# PDM.net
KiCad netlist of a schematic drawn in EAGLE
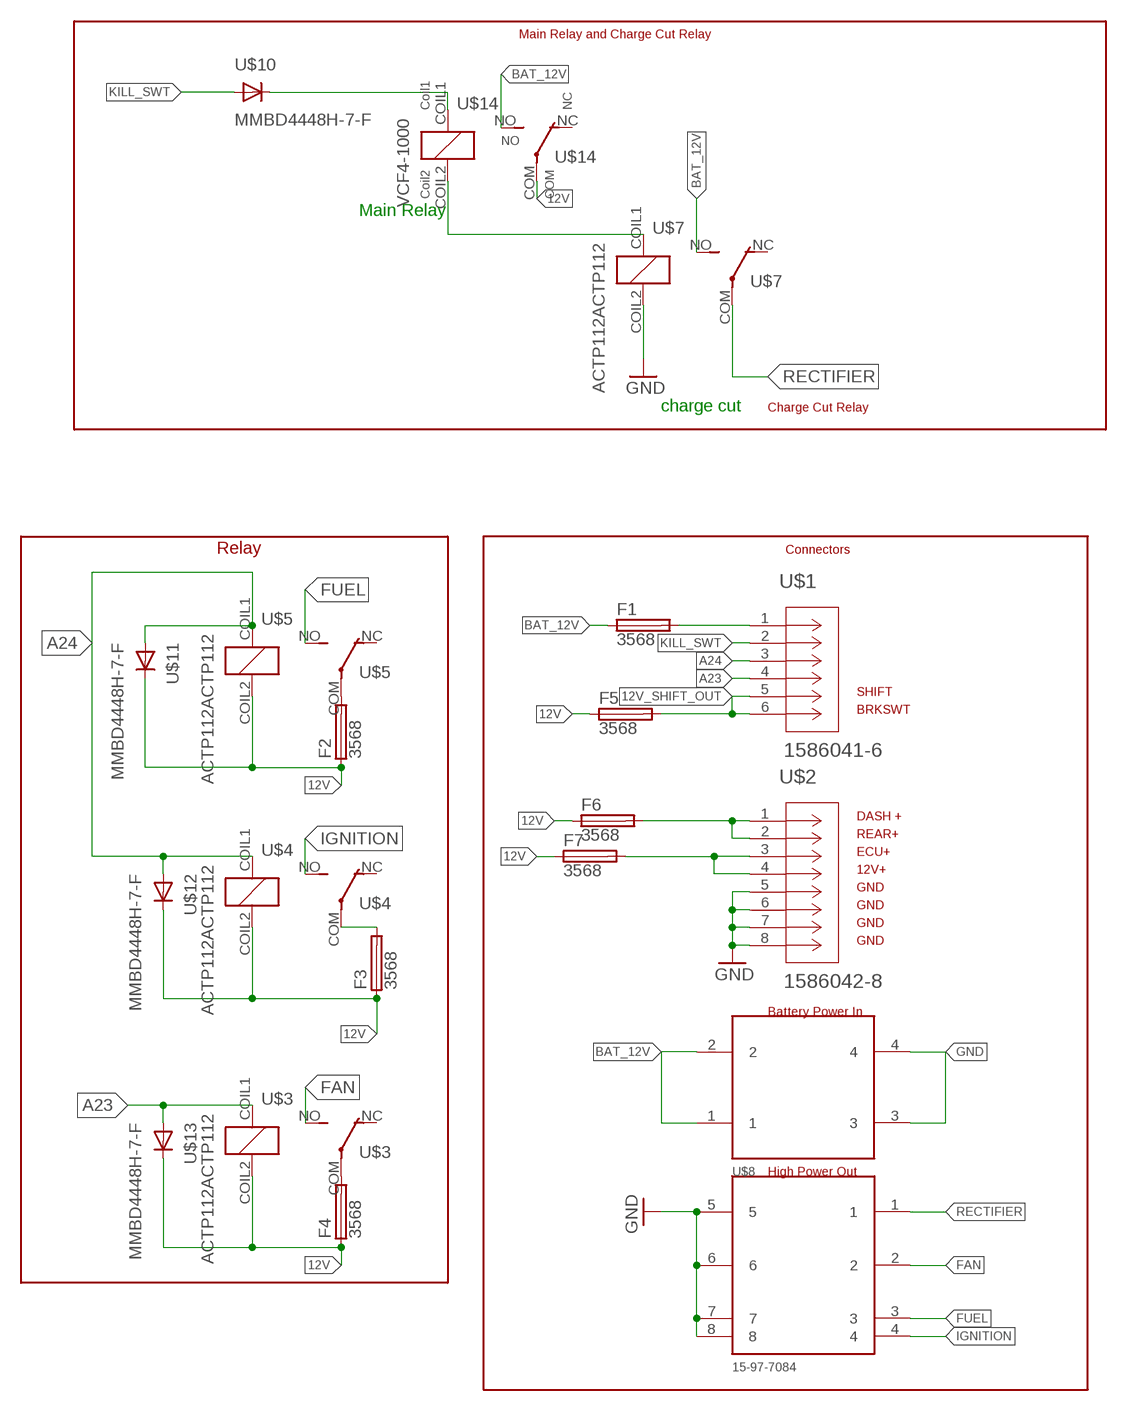
[diagram p0: schematic, sheet 1]

(export (version "E")
  (design (tool "Eeschema 10.0.6"))
  (components
    (comp (ref "F1")
      (value "3568")
      (footprint "eagle-import:3568")
      (libsource (lib "eagle-import") (part "3568"))
    )
    (comp (ref "F2")
      (value "3568")
      (footprint "eagle-import:3568")
      (libsource (lib "eagle-import") (part "3568"))
    )
    (comp (ref "F3")
      (value "3568")
      (footprint "eagle-import:3568")
      (libsource (lib "eagle-import") (part "3568"))
    )
    (comp (ref "F4")
      (value "3568")
      (footprint "eagle-import:3568")
      (libsource (lib "eagle-import") (part "3568"))
    )
    (comp (ref "F5")
      (value "3568")
      (footprint "eagle-import:3568")
      (libsource (lib "eagle-import") (part "3568"))
    )
    (comp (ref "F6")
      (value "3568")
      (footprint "eagle-import:3568")
      (libsource (lib "eagle-import") (part "3568"))
    )
    (comp (ref "F7")
      (value "3568")
      (footprint "eagle-import:3568")
      (libsource (lib "eagle-import") (part "3568"))
    )
    (comp (ref "U$1")
      (value "1586041-6")
      (footprint "eagle-import:1586041-6")
      (libsource (lib "eagle-import") (part "1586041-6"))
    )
    (comp (ref "U$2")
      (value "1586042-8")
      (footprint "eagle-import:1586042-8")
      (libsource (lib "eagle-import") (part "1586042-8"))
    )
    (comp (ref "U$3")
      (value "ACTP112ACTP112")
      (footprint "eagle-import:ACTP112")
      (libsource (lib "eagle-import") (part "ACTP112ACTP112"))
    )
    (comp (ref "U$4")
      (value "ACTP112ACTP112")
      (footprint "eagle-import:ACTP112")
      (libsource (lib "eagle-import") (part "ACTP112ACTP112"))
    )
    (comp (ref "U$5")
      (value "ACTP112ACTP112")
      (footprint "eagle-import:ACTP112")
      (libsource (lib "eagle-import") (part "ACTP112ACTP112"))
    )
    (comp (ref "U$7")
      (value "ACTP112ACTP112")
      (footprint "eagle-import:ACTP112")
      (libsource (lib "eagle-import") (part "ACTP112ACTP112"))
    )
    (comp (ref "U$8")
      (value "15-97-7084")
      (footprint "eagle-import:15-97-7084")
      (libsource (lib "eagle-import") (part "15-97-7084"))
    )
    (comp (ref "U$9")
      (value "15-97-8043")
      (footprint "eagle-import:15-97-8043")
      (libsource (lib "eagle-import") (part "15-97-8043"))
    )
    (comp (ref "U$10")
      (value "MMBD4448H-7-F")
      (footprint "eagle-import:SOT23-3")
      (libsource (lib "eagle-import") (part "MMBD4448H-7-F"))
    )
    (comp (ref "U$11")
      (value "MMBD4448H-7-F")
      (footprint "eagle-import:SOT23-3")
      (libsource (lib "eagle-import") (part "MMBD4448H-7-F"))
    )
    (comp (ref "U$12")
      (value "MMBD4448H-7-F")
      (footprint "eagle-import:SOT23-3")
      (libsource (lib "eagle-import") (part "MMBD4448H-7-F"))
    )
    (comp (ref "U$13")
      (value "MMBD4448H-7-F")
      (footprint "eagle-import:SOT23-3")
      (libsource (lib "eagle-import") (part "MMBD4448H-7-F"))
    )
    (comp (ref "U$14")
      (value "VCF4-1000")
      (footprint "eagle-import:VCF4-1000")
      (libsource (lib "eagle-import") (part "VCF4-1000"))
    )
  )
  (nets
    (net (code "1") (name "12V") (class "Default")
      (node (ref "F2") (pin "1") (pinfunction "1_1") (pintype "passive"))
      (node (ref "F2") (pin "2") (pinfunction "1_2") (pintype "passive"))
      (node (ref "F3") (pin "1") (pinfunction "1_1") (pintype "passive"))
      (node (ref "F3") (pin "2") (pinfunction "1_2") (pintype "passive"))
      (node (ref "F4") (pin "1") (pinfunction "1_1") (pintype "passive"))
      (node (ref "F4") (pin "2") (pinfunction "1_2") (pintype "passive"))
      (node (ref "F5") (pin "1") (pinfunction "1_1") (pintype "passive"))
      (node (ref "F5") (pin "2") (pinfunction "1_2") (pintype "passive"))
      (node (ref "F6") (pin "1") (pinfunction "1_1") (pintype "passive"))
      (node (ref "F6") (pin "2") (pinfunction "1_2") (pintype "passive"))
      (node (ref "F7") (pin "1") (pinfunction "1_1") (pintype "passive"))
      (node (ref "F7") (pin "2") (pinfunction "1_2") (pintype "passive"))
      (node (ref "U$11") (pin "3") (pinfunction "C_3") (pintype "passive"))
      (node (ref "U$12") (pin "3") (pinfunction "C_3") (pintype "passive"))
      (node (ref "U$13") (pin "3") (pinfunction "C_3") (pintype "passive"))
      (node (ref "U$14") (pin "COM") (pinfunction "COM_COM") (pintype "passive"))
      (node (ref "U$3") (pin "COIL2") (pinfunction "COIL2_COIL2") (pintype "passive"))
      (node (ref "U$4") (pin "COIL2") (pinfunction "COIL2_COIL2") (pintype "passive"))
      (node (ref "U$5") (pin "COIL2") (pinfunction "COIL2_COIL2") (pintype "passive"))
    )
    (net (code "2") (name "12V_SHIFT_OUT") (class "Default")
      (node (ref "F5") (pin "3") (pinfunction "2_3") (pintype "passive"))
      (node (ref "F5") (pin "4") (pinfunction "2_4") (pintype "passive"))
      (node (ref "U$1") (pin "5") (pinfunction "5_5") (pintype "passive"))
      (node (ref "U$1") (pin "6") (pinfunction "6_6") (pintype "passive"))
    )
    (net (code "3") (name "A23") (class "Default")
      (node (ref "U$1") (pin "4") (pinfunction "4_4") (pintype "passive"))
      (node (ref "U$13") (pin "1") (pinfunction "A_1") (pintype "passive"))
      (node (ref "U$3") (pin "COIL1") (pinfunction "COIL1_COIL1") (pintype "passive"))
    )
    (net (code "4") (name "A24") (class "Default")
      (node (ref "U$1") (pin "3") (pinfunction "3_3") (pintype "passive"))
      (node (ref "U$11") (pin "1") (pinfunction "A_1") (pintype "passive"))
      (node (ref "U$12") (pin "1") (pinfunction "A_1") (pintype "passive"))
      (node (ref "U$4") (pin "COIL1") (pinfunction "COIL1_COIL1") (pintype "passive"))
      (node (ref "U$5") (pin "COIL1") (pinfunction "COIL1_COIL1") (pintype "passive"))
    )
    (net (code "5") (name "BAT_12V") (class "Default")
      (node (ref "F1") (pin "1") (pinfunction "1_1") (pintype "passive"))
      (node (ref "F1") (pin "2") (pinfunction "1_2") (pintype "passive"))
      (node (ref "U$14") (pin "NO") (pinfunction "NO_NO") (pintype "passive"))
      (node (ref "U$7") (pin "NO") (pinfunction "NO_NO") (pintype "passive"))
      (node (ref "U$9") (pin "1") (pinfunction "1_1") (pintype "bidirectional"))
      (node (ref "U$9") (pin "2") (pinfunction "2_2") (pintype "bidirectional"))
    )
    (net (code "6") (name "FAN") (class "Default")
      (node (ref "U$3") (pin "NO") (pinfunction "NO_NO") (pintype "passive"))
      (node (ref "U$8") (pin "2") (pinfunction "2_2") (pintype "bidirectional"))
    )
    (net (code "7") (name "FUEL") (class "Default")
      (node (ref "U$5") (pin "NO") (pinfunction "NO_NO") (pintype "passive"))
      (node (ref "U$8") (pin "3") (pinfunction "3_3") (pintype "bidirectional"))
    )
    (net (code "8") (name "GND") (class "Default")
      (node (ref "U$2") (pin "5") (pinfunction "5_5") (pintype "passive"))
      (node (ref "U$2") (pin "6") (pinfunction "6_6") (pintype "passive"))
      (node (ref "U$2") (pin "7") (pinfunction "7_7") (pintype "passive"))
      (node (ref "U$2") (pin "8") (pinfunction "8_8") (pintype "passive"))
      (node (ref "U$7") (pin "COIL2") (pinfunction "COIL2_COIL2") (pintype "passive"))
      (node (ref "U$8") (pin "5") (pinfunction "5_5") (pintype "bidirectional"))
      (node (ref "U$8") (pin "6") (pinfunction "6_6") (pintype "bidirectional"))
      (node (ref "U$8") (pin "7") (pinfunction "7_7") (pintype "bidirectional"))
      (node (ref "U$8") (pin "8") (pinfunction "8_8") (pintype "bidirectional"))
      (node (ref "U$9") (pin "3") (pinfunction "3_3") (pintype "bidirectional"))
      (node (ref "U$9") (pin "4") (pinfunction "4_4") (pintype "bidirectional"))
    )
    (net (code "9") (name "IGNITION") (class "Default")
      (node (ref "U$4") (pin "NO") (pinfunction "NO_NO") (pintype "passive"))
      (node (ref "U$8") (pin "4") (pinfunction "4_4") (pintype "bidirectional"))
    )
    (net (code "10") (name "KILL_SWT") (class "Default")
      (node (ref "U$1") (pin "2") (pinfunction "2_2") (pintype "passive"))
      (node (ref "U$10") (pin "1") (pinfunction "A_1") (pintype "passive"))
    )
    (net (code "11") (name "Net-(F1-2-Pad3)") (class "Default")
      (node (ref "F1") (pin "3") (pinfunction "2_3") (pintype "passive"))
      (node (ref "F1") (pin "4") (pinfunction "2_4") (pintype "passive"))
      (node (ref "U$1") (pin "1") (pinfunction "1_1") (pintype "passive"))
    )
    (net (code "12") (name "Net-(F2-2-Pad3)") (class "Default")
      (node (ref "F2") (pin "3") (pinfunction "2_3") (pintype "passive"))
      (node (ref "F2") (pin "4") (pinfunction "2_4") (pintype "passive"))
      (node (ref "U$5") (pin "COM") (pinfunction "COM_COM") (pintype "passive"))
    )
    (net (code "13") (name "Net-(F3-2-Pad3)") (class "Default")
      (node (ref "F3") (pin "3") (pinfunction "2_3") (pintype "passive"))
      (node (ref "F3") (pin "4") (pinfunction "2_4") (pintype "passive"))
      (node (ref "U$4") (pin "COM") (pinfunction "COM_COM") (pintype "passive"))
    )
    (net (code "14") (name "Net-(F4-2-Pad3)") (class "Default")
      (node (ref "F4") (pin "3") (pinfunction "2_3") (pintype "passive"))
      (node (ref "F4") (pin "4") (pinfunction "2_4") (pintype "passive"))
      (node (ref "U$3") (pin "COM") (pinfunction "COM_COM") (pintype "passive"))
    )
    (net (code "15") (name "Net-(F6-2-Pad3)") (class "Default")
      (node (ref "F6") (pin "3") (pinfunction "2_3") (pintype "passive"))
      (node (ref "F6") (pin "4") (pinfunction "2_4") (pintype "passive"))
      (node (ref "U$2") (pin "1") (pinfunction "1_1") (pintype "passive"))
      (node (ref "U$2") (pin "2") (pinfunction "2_2") (pintype "passive"))
    )
    (net (code "16") (name "Net-(F7-2-Pad3)") (class "Default")
      (node (ref "F7") (pin "3") (pinfunction "2_3") (pintype "passive"))
      (node (ref "F7") (pin "4") (pinfunction "2_4") (pintype "passive"))
      (node (ref "U$2") (pin "3") (pinfunction "3_3") (pintype "passive"))
      (node (ref "U$2") (pin "4") (pinfunction "4_4") (pintype "passive"))
    )
    (net (code "17") (name "Net-(U$10-C)") (class "Default")
      (node (ref "U$10") (pin "3") (pinfunction "C_3") (pintype "passive"))
      (node (ref "U$14") (pin "COIL1") (pinfunction "COIL1_COIL1") (pintype "passive"))
    )
    (net (code "18") (name "Net-(U$14-PadCOIL2)") (class "Default")
      (node (ref "U$14") (pin "COIL2") (pinfunction "COIL2_COIL2") (pintype "passive"))
      (node (ref "U$7") (pin "COIL1") (pinfunction "COIL1_COIL1") (pintype "passive"))
    )
    (net (code "19") (name "RECTIFIER") (class "Default")
      (node (ref "U$7") (pin "COM") (pinfunction "COM_COM") (pintype "passive"))
      (node (ref "U$8") (pin "1") (pinfunction "1_1") (pintype "bidirectional"))
    )
    (net (code "20") (name "unconnected-(U$3-PadNC)") (class "Default")
      (node (ref "U$3") (pin "NC") (pinfunction "NC_NC") (pintype "passive"))
    )
    (net (code "21") (name "unconnected-(U$4-PadNC)") (class "Default")
      (node (ref "U$4") (pin "NC") (pinfunction "NC_NC") (pintype "passive"))
    )
    (net (code "22") (name "unconnected-(U$5-PadNC)") (class "Default")
      (node (ref "U$5") (pin "NC") (pinfunction "NC_NC") (pintype "passive"))
    )
    (net (code "23") (name "unconnected-(U$7-PadNC)") (class "Default")
      (node (ref "U$7") (pin "NC") (pinfunction "NC_NC") (pintype "passive"))
    )
    (net (code "24") (name "unconnected-(U$14-PadNC)") (class "Default")
      (node (ref "U$14") (pin "NC") (pinfunction "NC_NC") (pintype "passive"))
    )
  )
)
